# fonte3.net
KiCad netlist of a schematic drawn in EAGLE
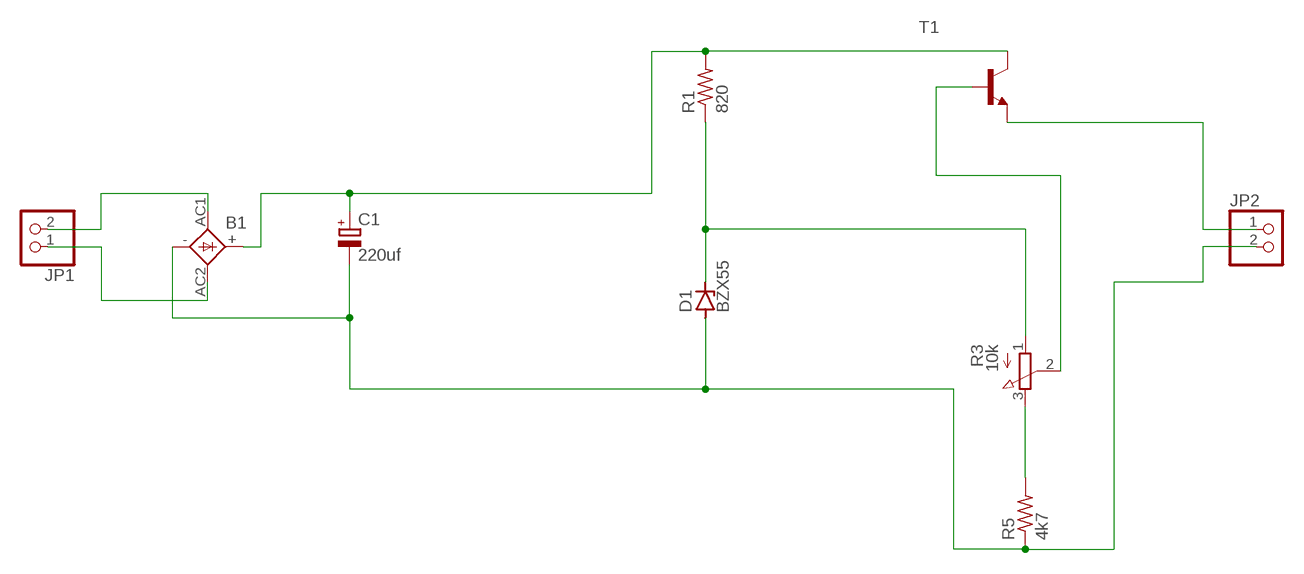
[diagram p0: schematic, sheet 1]

(export (version "E")
  (design (tool "Eeschema 10.0.6"))
  (components
    (comp (ref "B1")
      (value "1KAB")
      (footprint "eagle-import:1KAB")
      (libsource (lib "eagle-import") (part "1KAB"))
    )
    (comp (ref "C1")
      (value "220uf")
      (footprint "eagle-import:E5-10,5")
      (libsource (lib "eagle-import") (part "CPOL-EUE5-10.5"))
    )
    (comp (ref "D1")
      (value "BZX55")
      (footprint "eagle-import:DO35Z10")
      (libsource (lib "eagle-import") (part "BZX55"))
    )
    (comp (ref "JP1")
      (value "PINHD-1X2")
      (footprint "eagle-import:1X02")
      (libsource (lib "eagle-import") (part "PINHD-1X2"))
    )
    (comp (ref "JP2")
      (value "PINHD-1X2")
      (footprint "eagle-import:1X02")
      (libsource (lib "eagle-import") (part "PINHD-1X2"))
    )
    (comp (ref "R1")
      (value "820")
      (footprint "eagle-import:0309_12")
      (libsource (lib "eagle-import") (part "R-US_0309/12"))
    )
    (comp (ref "R3")
      (value "10k")
      (footprint "eagle-import:3RP_1610N")
      (libsource (lib "eagle-import") (part "3RP/1610N"))
    )
    (comp (ref "R5")
      (value "4k7")
      (footprint "eagle-import:0309_12")
      (libsource (lib "eagle-import") (part "R-US_0309/12"))
    )
    (comp (ref "T1")
      (value "-NPN-TO5")
      (footprint "eagle-import:TO5")
      (libsource (lib "eagle-import") (part "-NPN-TO5"))
    )
  )
  (nets
    (net (code "1") (name "Net-(B1-Pad-)") (class "Default")
      (node (ref "B1") (pin "-") (pinfunction "-_-") (pintype "passive"))
      (node (ref "C1") (pin "-") (pinfunction "-_-") (pintype "passive"))
      (node (ref "D1") (pin "A") (pinfunction "A_A") (pintype "passive"))
      (node (ref "JP2") (pin "2") (pinfunction "2_2") (pintype "passive"))
      (node (ref "R5") (pin "1") (pinfunction "1_1") (pintype "passive"))
    )
    (net (code "2") (name "Net-(B1-PadAC1)") (class "Default")
      (node (ref "B1") (pin "AC1") (pinfunction "AC1_AC1") (pintype "passive"))
      (node (ref "JP1") (pin "2") (pinfunction "2_2") (pintype "passive"))
    )
    (net (code "3") (name "Net-(B1-PadAC2)") (class "Default")
      (node (ref "B1") (pin "AC2") (pinfunction "AC2_AC2") (pintype "passive"))
      (node (ref "JP1") (pin "1") (pinfunction "1_1") (pintype "passive"))
    )
    (net (code "4") (name "Net-(R3-A)") (class "Default")
      (node (ref "D1") (pin "C") (pinfunction "C_C") (pintype "passive"))
      (node (ref "R1") (pin "1") (pinfunction "1_1") (pintype "passive"))
      (node (ref "R3") (pin "1") (pinfunction "A_1") (pintype "passive"))
    )
    (net (code "5") (name "Net-(R3-E)") (class "Default")
      (node (ref "R3") (pin "3") (pinfunction "E_3") (pintype "passive"))
      (node (ref "R5") (pin "2") (pinfunction "2_2") (pintype "passive"))
    )
    (net (code "6") (name "Net-(R3-S)") (class "Default")
      (node (ref "R3") (pin "2") (pinfunction "S_2") (pintype "passive"))
      (node (ref "T1") (pin "2") (pinfunction "B_2") (pintype "passive"))
    )
    (net (code "7") (name "Net-(T1-C)") (class "Default")
      (node (ref "B1") (pin "+") (pinfunction "+_+") (pintype "passive"))
      (node (ref "C1") (pin "+") (pinfunction "+_+") (pintype "passive"))
      (node (ref "R1") (pin "2") (pinfunction "2_2") (pintype "passive"))
      (node (ref "T1") (pin "3") (pinfunction "C_3") (pintype "passive"))
    )
    (net (code "8") (name "Net-(T1-E)") (class "Default")
      (node (ref "JP2") (pin "1") (pinfunction "1_1") (pintype "passive"))
      (node (ref "T1") (pin "1") (pinfunction "E_1") (pintype "passive"))
    )
  )
)
